# Driver.net
KiCad netlist of a schematic drawn in Altium Designer
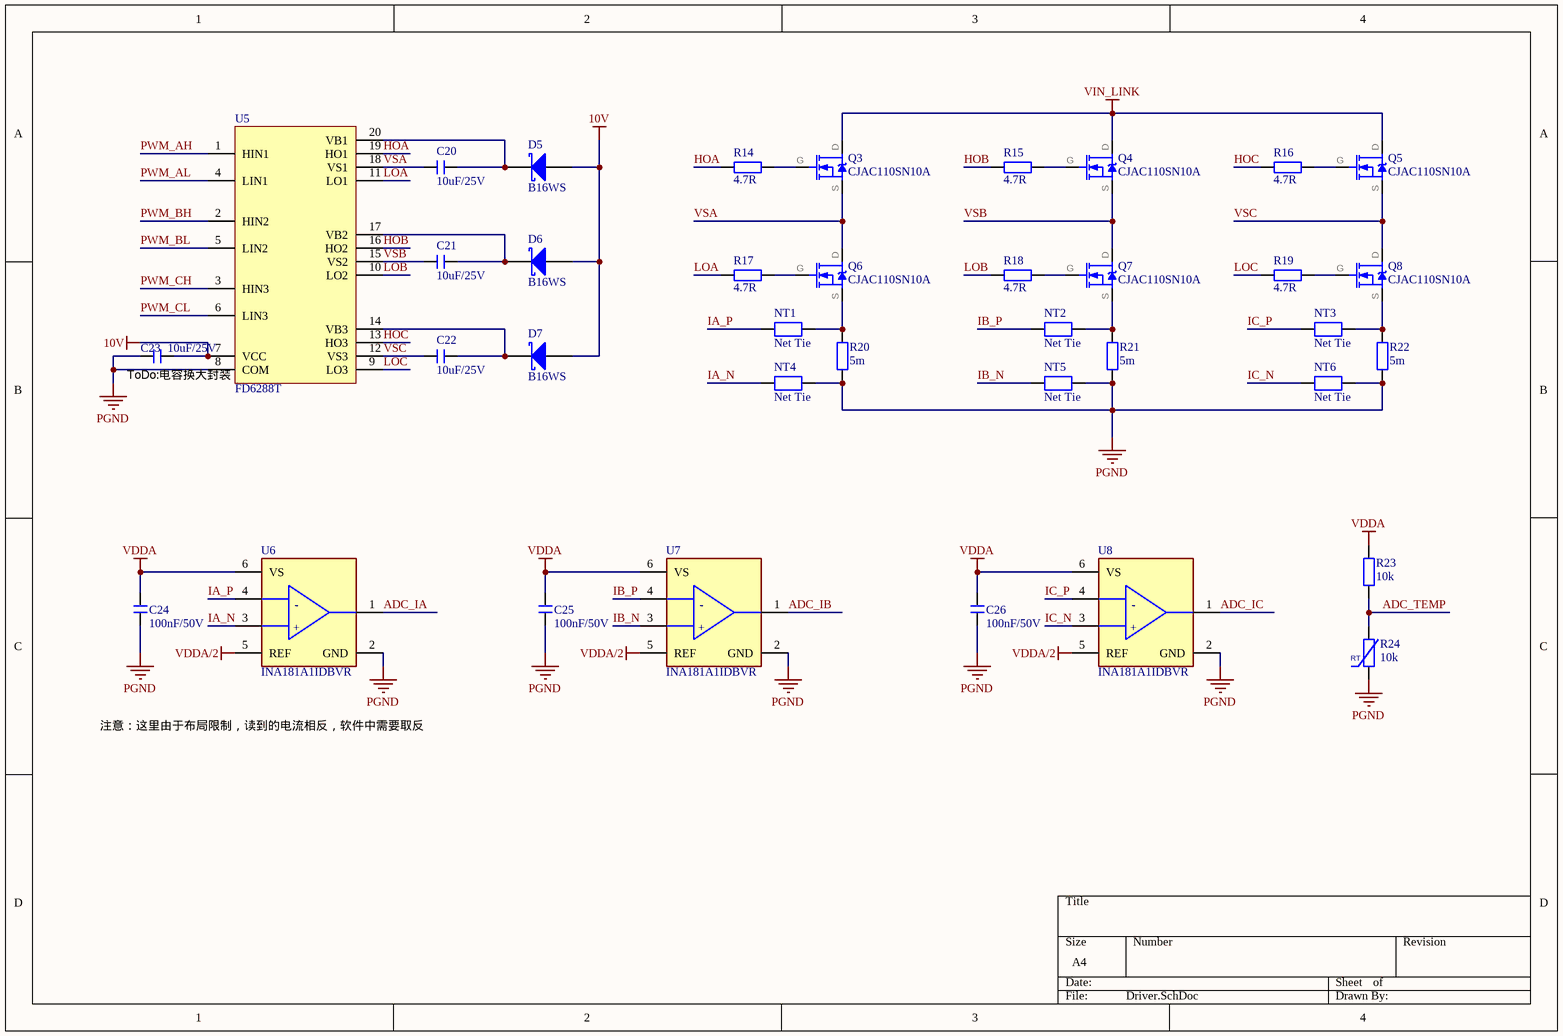
[diagram p0: Driver.SchDoc]

(export (version "E")
  (design (tool "Eeschema 10.0.6"))
  (components
    (comp (ref "C20")
      (value "10uF/25V")
      (footprint "Capacitor_0603_SMD")
      (description "无极性贴片电容")
      (fields (field (name "版权归属") "源创客"))
      (libsource (lib "源创客") (part "C"))
    )
    (comp (ref "C21")
      (value "10uF/25V")
      (footprint "Capacitor_0603_SMD")
      (description "无极性贴片电容")
      (fields (field (name "版权归属") "源创客"))
      (libsource (lib "源创客") (part "C"))
    )
    (comp (ref "C22")
      (value "10uF/25V")
      (footprint "Capacitor_0603_SMD")
      (description "无极性贴片电容")
      (fields (field (name "版权归属") "源创客"))
      (libsource (lib "源创客") (part "C"))
    )
    (comp (ref "C23")
      (value "10uF/25V")
      (footprint "Capacitor_0603_SMD")
      (description "无极性贴片电容")
      (fields (field (name "版权归属") "源创客"))
      (libsource (lib "源创客") (part "C"))
    )
    (comp (ref "C24")
      (value "100nF/50V")
      (footprint "Capacitor_0402_SMD")
      (description "无极性贴片电容")
      (fields (field (name "版权归属") "源创客"))
      (libsource (lib "源创客") (part "C"))
    )
    (comp (ref "C25")
      (value "100nF/50V")
      (footprint "Capacitor_0402_SMD")
      (description "无极性贴片电容")
      (fields (field (name "版权归属") "源创客"))
      (libsource (lib "源创客") (part "C"))
    )
    (comp (ref "C26")
      (value "100nF/50V")
      (footprint "Capacitor_0402_SMD")
      (description "无极性贴片电容")
      (fields (field (name "版权归属") "源创客"))
      (libsource (lib "源创客") (part "C"))
    )
    (comp (ref "D5")
      (value "B16WS")
      (footprint "SOD-323")
      (description "肖特基二极管")
      (libsource (lib "0.2 - 二极管-TVS-ESD-整流桥") (part "SS14"))
    )
    (comp (ref "D6")
      (value "B16WS")
      (footprint "SOD-323")
      (description "肖特基二极管")
      (libsource (lib "0.2 - 二极管-TVS-ESD-整流桥") (part "SS14"))
    )
    (comp (ref "D7")
      (value "B16WS")
      (footprint "SOD-323")
      (description "肖特基二极管")
      (libsource (lib "0.2 - 二极管-TVS-ESD-整流桥") (part "SS14"))
    )
    (comp (ref "NT1")
      (value "Net Tie")
      (footprint "Net Tie 10mil")
      (libsource (lib "Driver") (part "Net Tie"))
    )
    (comp (ref "NT2")
      (value "Net Tie")
      (footprint "Net Tie 10mil")
      (libsource (lib "Driver") (part "Net Tie"))
    )
    (comp (ref "NT3")
      (value "Net Tie")
      (footprint "Net Tie 10mil")
      (libsource (lib "Driver") (part "Net Tie"))
    )
    (comp (ref "NT4")
      (value "Net Tie")
      (footprint "Net Tie 10mil")
      (libsource (lib "Driver") (part "Net Tie"))
    )
    (comp (ref "NT5")
      (value "Net Tie")
      (footprint "Net Tie 10mil")
      (libsource (lib "Driver") (part "Net Tie"))
    )
    (comp (ref "NT6")
      (value "Net Tie")
      (footprint "Net Tie 10mil")
      (libsource (lib "Driver") (part "Net Tie"))
    )
    (comp (ref "Q3")
      (value "CJAC110SN10A")
      (footprint "PDFNWB5×6-8L")
      (description "110A 3.4mΩ@10V N-Channel Power MOSFET")
      (libsource (lib "Driver") (part "CJAC110SN10A"))
    )
    (comp (ref "Q4")
      (value "CJAC110SN10A")
      (footprint "PDFNWB5×6-8L")
      (description "110A 3.4mΩ@10V N-Channel Power MOSFET")
      (libsource (lib "Driver") (part "CJAC110SN10A"))
    )
    (comp (ref "Q5")
      (value "CJAC110SN10A")
      (footprint "PDFNWB5×6-8L")
      (description "110A 3.4mΩ@10V N-Channel Power MOSFET")
      (libsource (lib "Driver") (part "CJAC110SN10A"))
    )
    (comp (ref "Q6")
      (value "CJAC110SN10A")
      (footprint "PDFNWB5×6-8L")
      (description "110A 3.4mΩ@10V N-Channel Power MOSFET")
      (libsource (lib "Driver") (part "CJAC110SN10A"))
    )
    (comp (ref "Q7")
      (value "CJAC110SN10A")
      (footprint "PDFNWB5×6-8L")
      (description "110A 3.4mΩ@10V N-Channel Power MOSFET")
      (libsource (lib "Driver") (part "CJAC110SN10A"))
    )
    (comp (ref "Q8")
      (value "CJAC110SN10A")
      (footprint "PDFNWB5×6-8L")
      (description "110A 3.4mΩ@10V N-Channel Power MOSFET")
      (libsource (lib "Driver") (part "CJAC110SN10A"))
    )
    (comp (ref "R14")
      (value "4.7R")
      (footprint "Resistor_0603_SMD")
      (description "贴片电阻")
      (fields (field (name "版权归属") "源创客"))
      (libsource (lib "源创客") (part "R"))
    )
    (comp (ref "R15")
      (value "4.7R")
      (footprint "Resistor_0603_SMD")
      (description "贴片电阻")
      (fields (field (name "版权归属") "源创客"))
      (libsource (lib "源创客") (part "R"))
    )
    (comp (ref "R16")
      (value "4.7R")
      (footprint "Resistor_0603_SMD")
      (description "贴片电阻")
      (fields (field (name "版权归属") "源创客"))
      (libsource (lib "源创客") (part "R"))
    )
    (comp (ref "R17")
      (value "4.7R")
      (footprint "Resistor_0603_SMD")
      (description "贴片电阻")
      (fields (field (name "版权归属") "源创客"))
      (libsource (lib "源创客") (part "R"))
    )
    (comp (ref "R18")
      (value "4.7R")
      (footprint "Resistor_0603_SMD")
      (description "贴片电阻")
      (fields (field (name "版权归属") "源创客"))
      (libsource (lib "源创客") (part "R"))
    )
    (comp (ref "R19")
      (value "4.7R")
      (footprint "Resistor_0603_SMD")
      (description "贴片电阻")
      (fields (field (name "版权归属") "源创客"))
      (libsource (lib "源创客") (part "R"))
    )
    (comp (ref "R20")
      (value "5m")
      (footprint "Resistor_2512_SMD")
      (description "贴片电阻")
      (fields (field (name "版权归属") "源创客"))
      (libsource (lib "源创客") (part "R"))
    )
    (comp (ref "R21")
      (value "5m")
      (footprint "Resistor_2512_SMD")
      (description "贴片电阻")
      (fields (field (name "版权归属") "源创客"))
      (libsource (lib "源创客") (part "R"))
    )
    (comp (ref "R22")
      (value "5m")
      (footprint "Resistor_2512_SMD")
      (description "贴片电阻")
      (fields (field (name "版权归属") "源创客"))
      (libsource (lib "源创客") (part "R"))
    )
    (comp (ref "R23")
      (value "10k")
      (footprint "Resistor_0402_SMD")
      (description "贴片电阻")
      (libsource (lib "0.1 - 电阻-电容-电感-晶振-晶体-磁珠-电位器") (part "R"))
    )
    (comp (ref "R24")
      (value "10k")
      (footprint "Resistor_0402_SMD")
      (description "热敏电阻")
      (libsource (lib "0.1 - 电阻-电容-电感-晶振-晶体-磁珠-电位器") (part "RT"))
    )
    (comp (ref "U5")
      (value "FD6288T")
      (footprint "TSSOP20_L")
      (description "三相250V栅极驱动器")
      (libsource (lib "Driver") (part "FD6288T"))
    )
    (comp (ref "U6")
      (value "INA181A1IDBVR")
      (footprint "FP-DBV0006A-IPC_A")
      (description "IC CURR SENSE 1 CIRCUIT SOT23-6")
      (fields
        (field (name "OCTOPART") "https://octopart.com/ina181a1idbvr-texas+instruments-81856289")
        (field (name "MANUFACTURER") "Texas Instruments")
      )
      (libsource (lib "Altium Content Vault") (part "dd0ac0ae35b65eabf63b4a35b0ed67b"))
    )
    (comp (ref "U7")
      (value "INA181A1IDBVR")
      (footprint "FP-DBV0006A-IPC_A")
      (description "IC CURR SENSE 1 CIRCUIT SOT23-6")
      (fields
        (field (name "OCTOPART") "https://octopart.com/ina181a1idbvr-texas+instruments-81856289")
        (field (name "MANUFACTURER") "Texas Instruments")
      )
      (libsource (lib "Altium Content Vault") (part "dd0ac0ae35b65eabf63b4a35b0ed67b"))
    )
    (comp (ref "U8")
      (value "INA181A1IDBVR")
      (footprint "FP-DBV0006A-IPC_A")
      (description "IC CURR SENSE 1 CIRCUIT SOT23-6")
      (fields
        (field (name "OCTOPART") "https://octopart.com/ina181a1idbvr-texas+instruments-81856289")
        (field (name "MANUFACTURER") "Texas Instruments")
      )
      (libsource (lib "Altium Content Vault") (part "dd0ac0ae35b65eabf63b4a35b0ed67b"))
    )
  )
  (nets
    (net (code "1") (name "/ADC_IA") (class "Default")
      (node (ref "U6") (pin "1") (pinfunction "OUT_1") (pintype "passive"))
    )
    (net (code "2") (name "/ADC_IB") (class "Default")
      (node (ref "U7") (pin "1") (pinfunction "OUT_1") (pintype "passive"))
    )
    (net (code "3") (name "/ADC_IC") (class "Default")
      (node (ref "U8") (pin "1") (pinfunction "OUT_1") (pintype "passive"))
    )
    (net (code "4") (name "/ADC_TEMP") (class "Default")
      (node (ref "R23") (pin "1") (pinfunction "1_1") (pintype "passive"))
      (node (ref "R24") (pin "2") (pinfunction "2_2") (pintype "passive"))
    )
    (net (code "5") (name "/HOA") (class "Default")
      (node (ref "R14") (pin "2") (pinfunction "2_2") (pintype "passive"))
      (node (ref "U5") (pin "19") (pinfunction "HO1_19") (pintype "passive"))
    )
    (net (code "6") (name "/HOB") (class "Default")
      (node (ref "R15") (pin "2") (pinfunction "2_2") (pintype "passive"))
      (node (ref "U5") (pin "16") (pinfunction "HO2_16") (pintype "passive"))
    )
    (net (code "7") (name "/HOC") (class "Default")
      (node (ref "R16") (pin "2") (pinfunction "2_2") (pintype "passive"))
      (node (ref "U5") (pin "13") (pinfunction "HO3_13") (pintype "passive"))
    )
    (net (code "8") (name "/IA_N") (class "Default")
      (node (ref "NT4") (pin "1") (pinfunction "1_1") (pintype "passive"))
      (node (ref "U6") (pin "3") (pinfunction "IN+_3") (pintype "tri_state"))
    )
    (net (code "9") (name "/IA_P") (class "Default")
      (node (ref "NT1") (pin "1") (pinfunction "1_1") (pintype "passive"))
      (node (ref "U6") (pin "4") (pinfunction "IN-_4") (pintype "tri_state"))
    )
    (net (code "10") (name "/IB_N") (class "Default")
      (node (ref "NT5") (pin "1") (pinfunction "1_1") (pintype "passive"))
      (node (ref "U7") (pin "3") (pinfunction "IN+_3") (pintype "tri_state"))
    )
    (net (code "11") (name "/IB_P") (class "Default")
      (node (ref "NT2") (pin "1") (pinfunction "1_1") (pintype "passive"))
      (node (ref "U7") (pin "4") (pinfunction "IN-_4") (pintype "tri_state"))
    )
    (net (code "12") (name "/IC_N") (class "Default")
      (node (ref "NT6") (pin "1") (pinfunction "1_1") (pintype "passive"))
      (node (ref "U8") (pin "3") (pinfunction "IN+_3") (pintype "tri_state"))
    )
    (net (code "13") (name "/IC_P") (class "Default")
      (node (ref "NT3") (pin "1") (pinfunction "1_1") (pintype "passive"))
      (node (ref "U8") (pin "4") (pinfunction "IN-_4") (pintype "tri_state"))
    )
    (net (code "14") (name "/LOA") (class "Default")
      (node (ref "R17") (pin "2") (pinfunction "2_2") (pintype "passive"))
      (node (ref "U5") (pin "11") (pinfunction "LO1_11") (pintype "passive"))
    )
    (net (code "15") (name "/LOB") (class "Default")
      (node (ref "R18") (pin "2") (pinfunction "2_2") (pintype "passive"))
      (node (ref "U5") (pin "10") (pinfunction "LO2_10") (pintype "passive"))
    )
    (net (code "16") (name "/LOC") (class "Default")
      (node (ref "R19") (pin "2") (pinfunction "2_2") (pintype "passive"))
      (node (ref "U5") (pin "9") (pinfunction "LO3_9") (pintype "passive"))
    )
    (net (code "17") (name "/PWM_AH") (class "Default")
      (node (ref "U5") (pin "1") (pinfunction "HIN1_1") (pintype "passive"))
    )
    (net (code "18") (name "/PWM_AL") (class "Default")
      (node (ref "U5") (pin "4") (pinfunction "LIN1_4") (pintype "passive"))
    )
    (net (code "19") (name "/PWM_BH") (class "Default")
      (node (ref "U5") (pin "2") (pinfunction "HIN2_2") (pintype "passive"))
    )
    (net (code "20") (name "/PWM_BL") (class "Default")
      (node (ref "U5") (pin "5") (pinfunction "LIN2_5") (pintype "passive"))
    )
    (net (code "21") (name "/PWM_CH") (class "Default")
      (node (ref "U5") (pin "3") (pinfunction "HIN3_3") (pintype "passive"))
    )
    (net (code "22") (name "/PWM_CL") (class "Default")
      (node (ref "U5") (pin "6") (pinfunction "LIN3_6") (pintype "passive"))
    )
    (net (code "23") (name "/VSA") (class "Default")
      (node (ref "C20") (pin "1") (pinfunction "1_1") (pintype "passive"))
      (node (ref "Q3") (pin "S") (pinfunction "S_S") (pintype "passive"))
      (node (ref "Q6") (pin "D") (pinfunction "D_D") (pintype "passive"))
      (node (ref "U5") (pin "18") (pinfunction "VS1_18") (pintype "passive"))
    )
    (net (code "24") (name "/VSB") (class "Default")
      (node (ref "C21") (pin "1") (pinfunction "1_1") (pintype "passive"))
      (node (ref "Q4") (pin "S") (pinfunction "S_S") (pintype "passive"))
      (node (ref "Q7") (pin "D") (pinfunction "D_D") (pintype "passive"))
      (node (ref "U5") (pin "15") (pinfunction "VS2_15") (pintype "passive"))
    )
    (net (code "25") (name "/VSC") (class "Default")
      (node (ref "C22") (pin "1") (pinfunction "1_1") (pintype "passive"))
      (node (ref "Q5") (pin "S") (pinfunction "S_S") (pintype "passive"))
      (node (ref "Q8") (pin "D") (pinfunction "D_D") (pintype "passive"))
      (node (ref "U5") (pin "12") (pinfunction "VS3_12") (pintype "passive"))
    )
    (net (code "26") (name "10V") (class "Default")
      (node (ref "C23") (pin "2") (pinfunction "2_2") (pintype "passive"))
      (node (ref "D5") (pin "1") (pinfunction "A_1") (pintype "passive"))
      (node (ref "D6") (pin "1") (pinfunction "A_1") (pintype "passive"))
      (node (ref "D7") (pin "1") (pinfunction "A_1") (pintype "passive"))
      (node (ref "U5") (pin "7") (pinfunction "VCC_7") (pintype "passive"))
    )
    (net (code "27") (name "Net-(D5-K)") (class "Default")
      (node (ref "C20") (pin "2") (pinfunction "2_2") (pintype "passive"))
      (node (ref "D5") (pin "2") (pinfunction "K_2") (pintype "passive"))
      (node (ref "U5") (pin "20") (pinfunction "VB1_20") (pintype "passive"))
    )
    (net (code "28") (name "Net-(D6-K)") (class "Default")
      (node (ref "C21") (pin "2") (pinfunction "2_2") (pintype "passive"))
      (node (ref "D6") (pin "2") (pinfunction "K_2") (pintype "passive"))
      (node (ref "U5") (pin "17") (pinfunction "VB2_17") (pintype "passive"))
    )
    (net (code "29") (name "Net-(D7-K)") (class "Default")
      (node (ref "C22") (pin "2") (pinfunction "2_2") (pintype "passive"))
      (node (ref "D7") (pin "2") (pinfunction "K_2") (pintype "passive"))
      (node (ref "U5") (pin "14") (pinfunction "VB3_14") (pintype "passive"))
    )
    (net (code "30") (name "Net-(NT1-Pad2)") (class "Default")
      (node (ref "NT1") (pin "2") (pinfunction "2_2") (pintype "passive"))
      (node (ref "Q6") (pin "S") (pinfunction "S_S") (pintype "passive"))
      (node (ref "R20") (pin "2") (pinfunction "2_2") (pintype "passive"))
    )
    (net (code "31") (name "Net-(NT2-Pad2)") (class "Default")
      (node (ref "NT2") (pin "2") (pinfunction "2_2") (pintype "passive"))
      (node (ref "Q7") (pin "S") (pinfunction "S_S") (pintype "passive"))
      (node (ref "R21") (pin "2") (pinfunction "2_2") (pintype "passive"))
    )
    (net (code "32") (name "Net-(NT3-Pad2)") (class "Default")
      (node (ref "NT3") (pin "2") (pinfunction "2_2") (pintype "passive"))
      (node (ref "Q8") (pin "S") (pinfunction "S_S") (pintype "passive"))
      (node (ref "R22") (pin "2") (pinfunction "2_2") (pintype "passive"))
    )
    (net (code "33") (name "Net-(Q3-PadG)") (class "Default")
      (node (ref "Q3") (pin "G") (pinfunction "G_G") (pintype "passive"))
      (node (ref "R14") (pin "1") (pinfunction "1_1") (pintype "passive"))
    )
    (net (code "34") (name "Net-(Q4-PadG)") (class "Default")
      (node (ref "Q4") (pin "G") (pinfunction "G_G") (pintype "passive"))
      (node (ref "R15") (pin "1") (pinfunction "1_1") (pintype "passive"))
    )
    (net (code "35") (name "Net-(Q5-PadG)") (class "Default")
      (node (ref "Q5") (pin "G") (pinfunction "G_G") (pintype "passive"))
      (node (ref "R16") (pin "1") (pinfunction "1_1") (pintype "passive"))
    )
    (net (code "36") (name "Net-(Q6-PadG)") (class "Default")
      (node (ref "Q6") (pin "G") (pinfunction "G_G") (pintype "passive"))
      (node (ref "R17") (pin "1") (pinfunction "1_1") (pintype "passive"))
    )
    (net (code "37") (name "Net-(Q7-PadG)") (class "Default")
      (node (ref "Q7") (pin "G") (pinfunction "G_G") (pintype "passive"))
      (node (ref "R18") (pin "1") (pinfunction "1_1") (pintype "passive"))
    )
    (net (code "38") (name "Net-(Q8-PadG)") (class "Default")
      (node (ref "Q8") (pin "G") (pinfunction "G_G") (pintype "passive"))
      (node (ref "R19") (pin "1") (pinfunction "1_1") (pintype "passive"))
    )
    (net (code "39") (name "PGND") (class "Default")
      (node (ref "C23") (pin "1") (pinfunction "1_1") (pintype "passive"))
      (node (ref "C24") (pin "1") (pinfunction "1_1") (pintype "passive"))
      (node (ref "C25") (pin "1") (pinfunction "1_1") (pintype "passive"))
      (node (ref "C26") (pin "1") (pinfunction "1_1") (pintype "passive"))
      (node (ref "NT4") (pin "2") (pinfunction "2_2") (pintype "passive"))
      (node (ref "NT5") (pin "2") (pinfunction "2_2") (pintype "passive"))
      (node (ref "NT6") (pin "2") (pinfunction "2_2") (pintype "passive"))
      (node (ref "R20") (pin "1") (pinfunction "1_1") (pintype "passive"))
      (node (ref "R21") (pin "1") (pinfunction "1_1") (pintype "passive"))
      (node (ref "R22") (pin "1") (pinfunction "1_1") (pintype "passive"))
      (node (ref "R24") (pin "1") (pinfunction "1_1") (pintype "passive"))
      (node (ref "U5") (pin "8") (pinfunction "COM_8") (pintype "passive"))
      (node (ref "U6") (pin "2") (pinfunction "GND_2") (pintype "power_in"))
      (node (ref "U7") (pin "2") (pinfunction "GND_2") (pintype "power_in"))
      (node (ref "U8") (pin "2") (pinfunction "GND_2") (pintype "power_in"))
    )
    (net (code "40") (name "VDDA") (class "Default")
      (node (ref "C24") (pin "2") (pinfunction "2_2") (pintype "passive"))
      (node (ref "C25") (pin "2") (pinfunction "2_2") (pintype "passive"))
      (node (ref "C26") (pin "2") (pinfunction "2_2") (pintype "passive"))
      (node (ref "R23") (pin "2") (pinfunction "2_2") (pintype "passive"))
      (node (ref "U6") (pin "6") (pinfunction "VS_6") (pintype "power_in"))
      (node (ref "U7") (pin "6") (pinfunction "VS_6") (pintype "power_in"))
      (node (ref "U8") (pin "6") (pinfunction "VS_6") (pintype "power_in"))
    )
    (net (code "41") (name "VDDA{slash}2") (class "Default")
      (node (ref "U6") (pin "5") (pinfunction "REF_5") (pintype "passive"))
      (node (ref "U7") (pin "5") (pinfunction "REF_5") (pintype "passive"))
      (node (ref "U8") (pin "5") (pinfunction "REF_5") (pintype "passive"))
    )
    (net (code "42") (name "VIN_LINK") (class "Default")
      (node (ref "Q3") (pin "D") (pinfunction "D_D") (pintype "passive"))
      (node (ref "Q4") (pin "D") (pinfunction "D_D") (pintype "passive"))
      (node (ref "Q5") (pin "D") (pinfunction "D_D") (pintype "passive"))
    )
  )
)
